# SCH_AQUVIS-Power_2023-07-29.net
KiCad netlist of a schematic drawn in EasyEDA
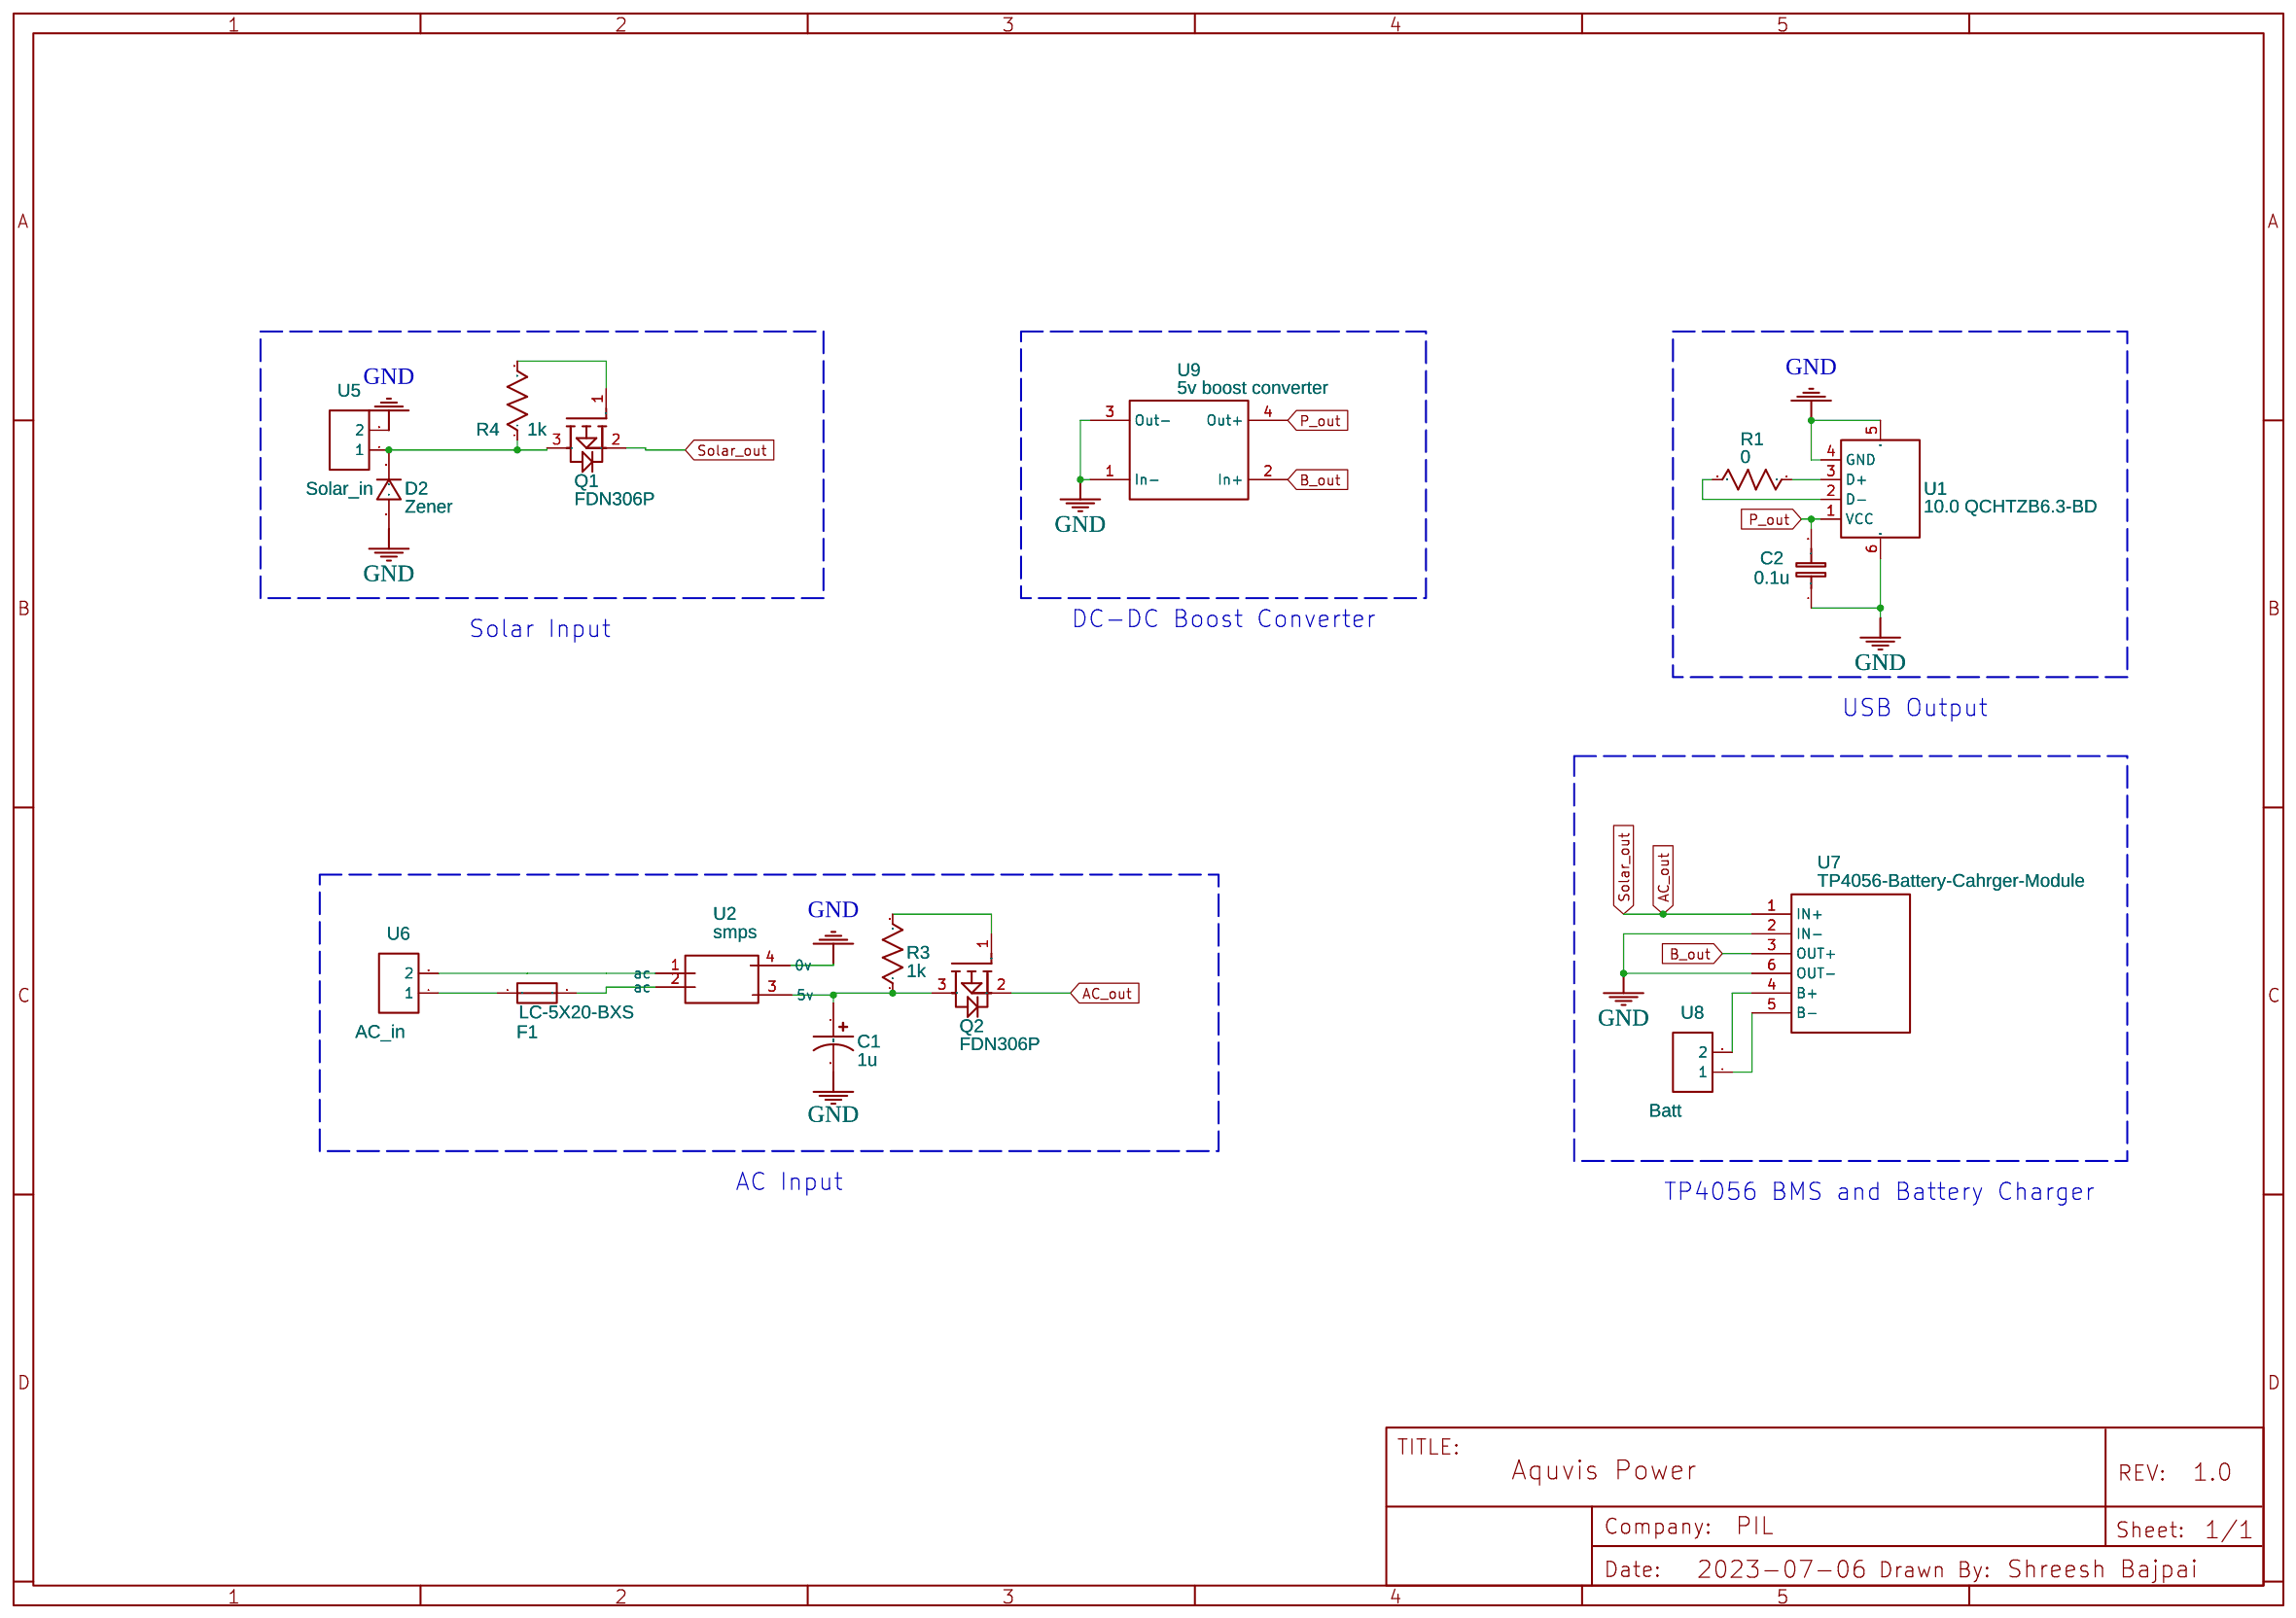
[diagram p0: schematic sheet]

(export (version "E")
  (design (tool "Eeschema 10.0.6"))
  (components
    (comp (ref "C1") (value "1u") (libsource (lib "") (part "CE_TH_D3.0×F1.5_US")))
    (comp (ref "C2") (value "0.1u") (libsource (lib "") (part "C_RAD-0.1_EU")))
    (comp (ref "D2")
      (value "Zener")
      (fields (field (name "Manufacturer Part") "1N4148") (field (name "Manufacturer") "STMicroelectronics"))
      (libsource (lib "") (part "1N4148"))
    )
    (comp (ref "F1")
      (value "LC-5X20-BXS")
      (fields (field (name "Manufacturer Part") "LC-5x20-BXS"))
      (libsource (lib "") (part "LC-5X20-BXS"))
    )
    (comp (ref "Q1") (value "FDN306P") (libsource (lib "") (part "FDN306P")))
    (comp (ref "Q2") (value "FDN306P") (libsource (lib "") (part "FDN306P")))
    (comp (ref "R1") (value "0") (libsource (lib "") (part "R_0805_US")))
    (comp (ref "R3") (value "1k") (libsource (lib "") (part "R_AXIAL-0.3_US")))
    (comp (ref "R4") (value "1k") (libsource (lib "") (part "R_AXIAL-0.3_US")))
    (comp (ref "U1")
      (value "10.0 QCHTZB6.3-BD")
      (fields (field (name "Manufacturer") "SHOU HAN(首韩)"))
      (libsource (lib "") (part "10.0 QCHTZB6.3-BD"))
    )
    (comp (ref "U2")
      (value "smps")
      (fields (field (name "Manufacturer Part") "5V"))
      (libsource (lib "") (part "smps123"))
    )
    (comp (ref "U5") (value "Solar_in") (libsource (lib "") (part "TERMINAL BLOCK 2P")))
    (comp (ref "U6") (value "AC_in") (libsource (lib "") (part "TERMINAL BLOCK 2P")))
    (comp (ref "U7")
      (value "TP4056-Battery-Cahrger-Module")
      (libsource (lib "") (part "TP4056-Battery-Cahrger-Module"))
    )
    (comp (ref "U8") (value "Batt") (libsource (lib "") (part "TERMINAL BLOCK 2P")))
    (comp (ref "U9") (value "5v boost converter") (libsource (lib "") (part "5v boost converter")))
  )
  (nets
    (net (code "1") (name "AC_out") (class "Default")
      (node (ref "Q1") (pin "2") (pinfunction "S_2") (pintype "input"))
      (node (ref "Q2") (pin "2") (pinfunction "S_2") (pintype "input"))
      (node (ref "U7") (pin "1") (pinfunction "IN+_1") (pintype "unspecified"))
    )
    (net (code "2") (name "B_out") (class "Default")
      (node (ref "U7") (pin "3") (pinfunction "OUT+_3") (pintype "unspecified"))
      (node (ref "U9") (pin "2") (pinfunction "In+_2") (pintype "unspecified"))
    )
    (net (code "3") (name "GND") (class "Default")
      (node (ref "C1") (pin "2") (pinfunction "2_2") (pintype "unspecified"))
      (node (ref "C2") (pin "1") (pinfunction "1_1") (pintype "unspecified"))
      (node (ref "D2") (pin "2") (pinfunction "2_2") (pintype "unspecified"))
      (node (ref "U1") (pin "4") (pinfunction "GND_4") (pintype "input"))
      (node (ref "U1") (pin "5") (pinfunction "SH1_5") (pintype "unspecified"))
      (node (ref "U1") (pin "6") (pinfunction "SH2_6") (pintype "unspecified"))
      (node (ref "U2") (pin "4") (pinfunction "0v_4") (pintype "output"))
      (node (ref "U5") (pin "2") (pinfunction "2_2") (pintype "unspecified"))
      (node (ref "U7") (pin "2") (pinfunction "IN-_2") (pintype "unspecified"))
      (node (ref "U7") (pin "6") (pinfunction "OUT-_6") (pintype "unspecified"))
      (node (ref "U9") (pin "1") (pinfunction "In-_1") (pintype "unspecified"))
      (node (ref "U9") (pin "3") (pinfunction "Out-_3") (pintype "unspecified"))
    )
    (net (code "4") (name "Net-(F1-Pad1)") (class "Default")
      (node (ref "F1") (pin "1") (pinfunction "1_1") (pintype "unspecified"))
      (node (ref "U6") (pin "1") (pinfunction "1_1") (pintype "unspecified"))
    )
    (net (code "5") (name "Net-(F1-Pad2)") (class "Default")
      (node (ref "F1") (pin "2") (pinfunction "2_2") (pintype "unspecified"))
      (node (ref "U2") (pin "2") (pinfunction "ac_2") (pintype "input"))
    )
    (net (code "6") (name "Net-(Q1-D)") (class "Default")
      (node (ref "D2") (pin "1") (pinfunction "1_1") (pintype "unspecified"))
      (node (ref "Q1") (pin "3") (pinfunction "D_3") (pintype "input"))
      (node (ref "R4") (pin "1") (pinfunction "1_1") (pintype "unspecified"))
      (node (ref "U5") (pin "1") (pinfunction "1_1") (pintype "unspecified"))
    )
    (net (code "7") (name "Net-(Q1-G)") (class "Default")
      (node (ref "Q1") (pin "1") (pinfunction "G_1") (pintype "input"))
      (node (ref "R4") (pin "2") (pinfunction "2_2") (pintype "unspecified"))
    )
    (net (code "8") (name "Net-(Q2-D)") (class "Default")
      (node (ref "C1") (pin "1") (pinfunction "1_1") (pintype "unspecified"))
      (node (ref "Q2") (pin "3") (pinfunction "D_3") (pintype "input"))
      (node (ref "R3") (pin "1") (pinfunction "1_1") (pintype "unspecified"))
      (node (ref "U2") (pin "3") (pinfunction "5v_3") (pintype "output"))
    )
    (net (code "9") (name "Net-(Q2-G)") (class "Default")
      (node (ref "Q2") (pin "1") (pinfunction "G_1") (pintype "input"))
      (node (ref "R3") (pin "2") (pinfunction "2_2") (pintype "unspecified"))
    )
    (net (code "10") (name "Net-(U1-D+)") (class "Default")
      (node (ref "R1") (pin "1") (pinfunction "1_1") (pintype "unspecified"))
      (node (ref "U1") (pin "3") (pinfunction "D+_3") (pintype "input"))
    )
    (net (code "11") (name "Net-(U1-D-)") (class "Default")
      (node (ref "R1") (pin "2") (pinfunction "2_2") (pintype "unspecified"))
      (node (ref "U1") (pin "2") (pinfunction "D-_2") (pintype "input"))
    )
    (net (code "12") (name "Net-(U2-ac-Pad1)") (class "Default")
      (node (ref "U2") (pin "1") (pinfunction "ac_1") (pintype "input"))
      (node (ref "U6") (pin "2") (pinfunction "2_2") (pintype "unspecified"))
    )
    (net (code "13") (name "Net-(U7-B+)") (class "Default")
      (node (ref "U7") (pin "4") (pinfunction "B+_4") (pintype "unspecified"))
      (node (ref "U8") (pin "2") (pinfunction "2_2") (pintype "unspecified"))
    )
    (net (code "14") (name "Net-(U7-B-)") (class "Default")
      (node (ref "U7") (pin "5") (pinfunction "B-_5") (pintype "unspecified"))
      (node (ref "U8") (pin "1") (pinfunction "1_1") (pintype "unspecified"))
    )
    (net (code "15") (name "P_out") (class "Default")
      (node (ref "C2") (pin "2") (pinfunction "2_2") (pintype "unspecified"))
      (node (ref "U1") (pin "1") (pinfunction "VCC_1") (pintype "input"))
      (node (ref "U9") (pin "4") (pinfunction "Out+_4") (pintype "unspecified"))
    )
  )
)
